# terminator.net
KiCad netlist of a schematic drawn in EAGLE
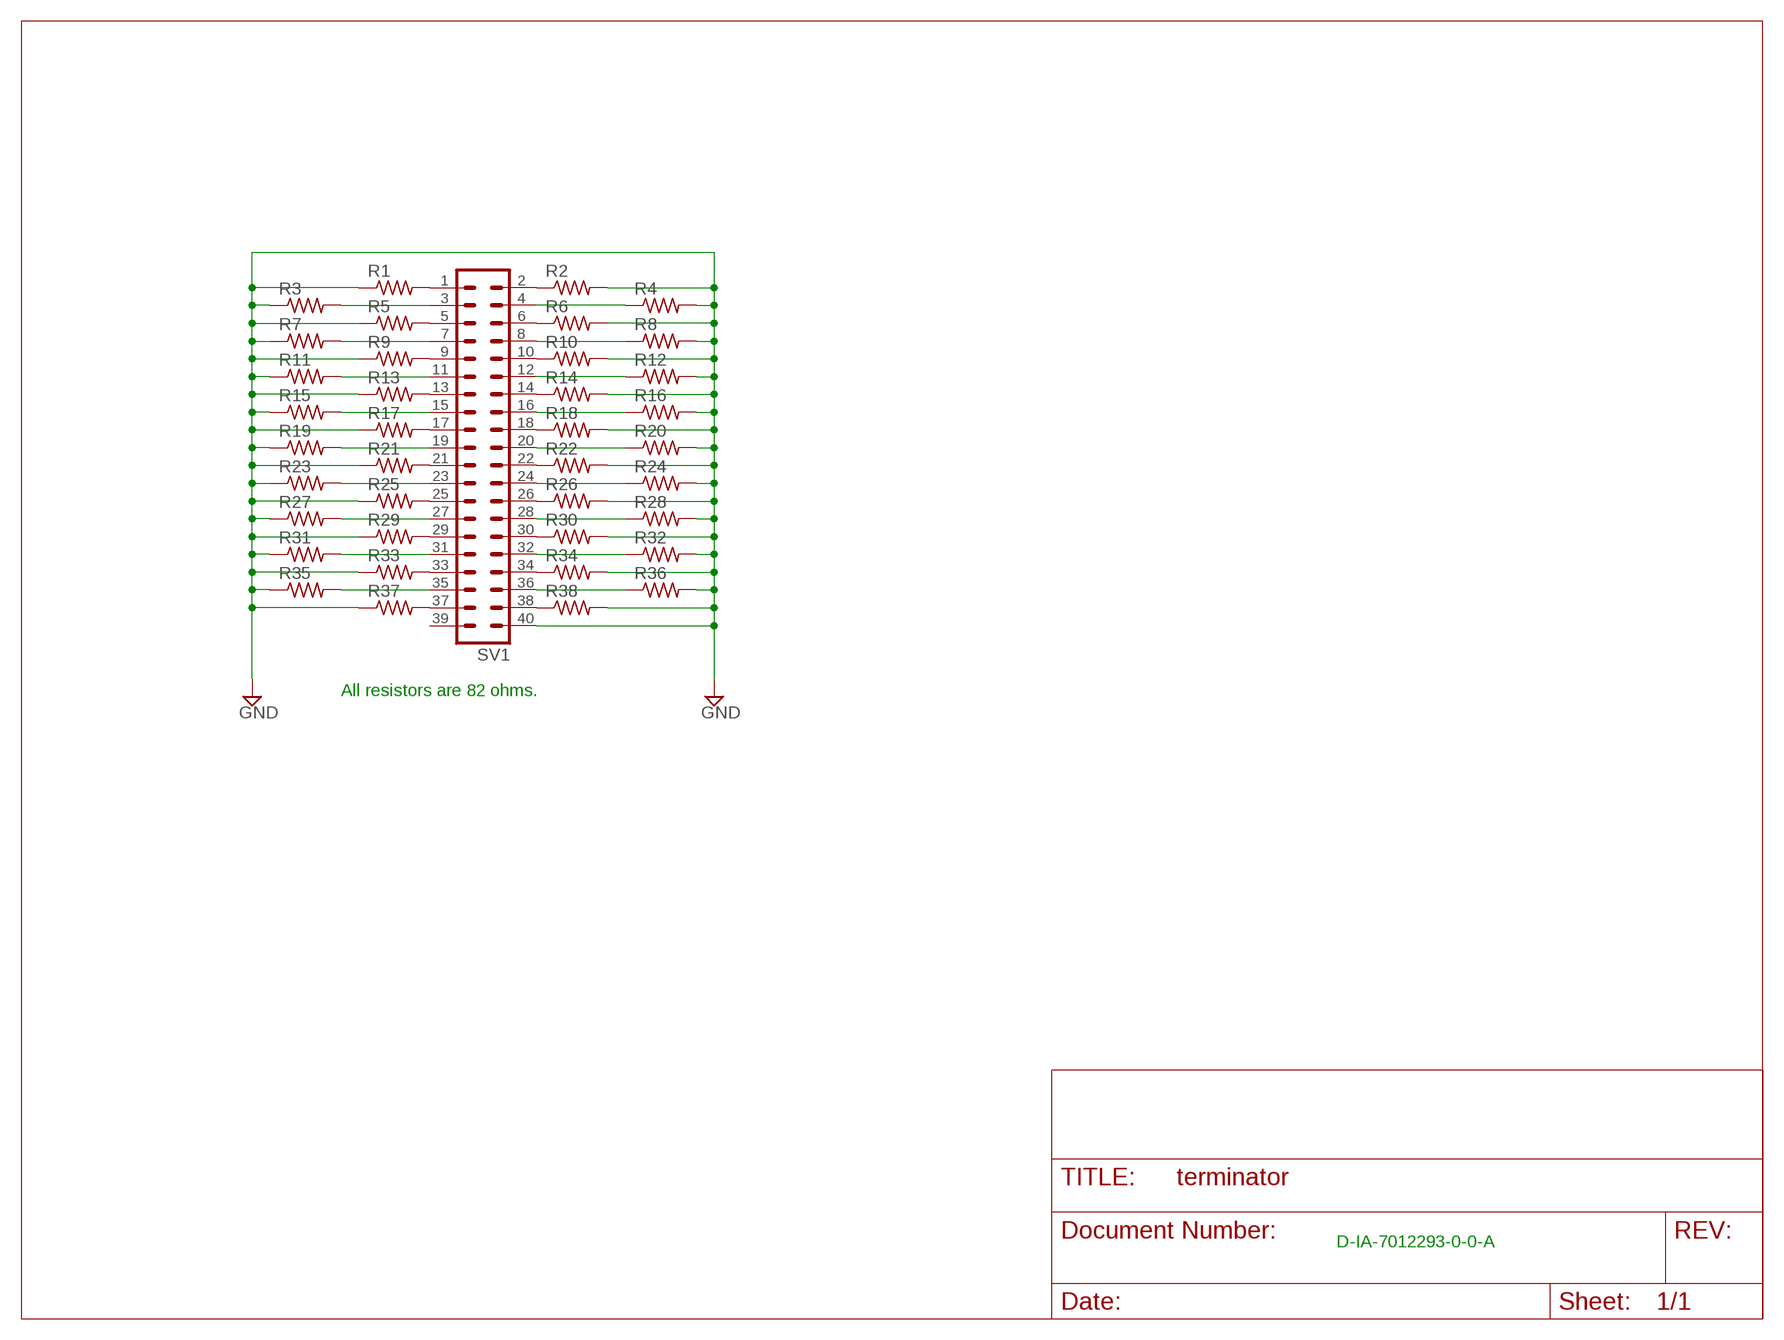
[diagram p0: schematic, sheet 1]

(export (version "E")
  (design (tool "Eeschema 10.0.6"))
  (components
    (comp (ref "R1")
      (value "R-US_M0805")
      (footprint "eagle-import:M0805")
      (libsource (lib "eagle-import") (part "R-US_M0805"))
    )
    (comp (ref "R2")
      (value "R-US_M0805")
      (footprint "eagle-import:M0805")
      (libsource (lib "eagle-import") (part "R-US_M0805"))
    )
    (comp (ref "R3")
      (value "R-US_M0805")
      (footprint "eagle-import:M0805")
      (libsource (lib "eagle-import") (part "R-US_M0805"))
    )
    (comp (ref "R4")
      (value "R-US_M0805")
      (footprint "eagle-import:M0805")
      (libsource (lib "eagle-import") (part "R-US_M0805"))
    )
    (comp (ref "R5")
      (value "R-US_M0805")
      (footprint "eagle-import:M0805")
      (libsource (lib "eagle-import") (part "R-US_M0805"))
    )
    (comp (ref "R6")
      (value "R-US_M0805")
      (footprint "eagle-import:M0805")
      (libsource (lib "eagle-import") (part "R-US_M0805"))
    )
    (comp (ref "R7")
      (value "R-US_M0805")
      (footprint "eagle-import:M0805")
      (libsource (lib "eagle-import") (part "R-US_M0805"))
    )
    (comp (ref "R8")
      (value "R-US_M0805")
      (footprint "eagle-import:M0805")
      (libsource (lib "eagle-import") (part "R-US_M0805"))
    )
    (comp (ref "R9")
      (value "R-US_M0805")
      (footprint "eagle-import:M0805")
      (libsource (lib "eagle-import") (part "R-US_M0805"))
    )
    (comp (ref "R10")
      (value "R-US_M0805")
      (footprint "eagle-import:M0805")
      (libsource (lib "eagle-import") (part "R-US_M0805"))
    )
    (comp (ref "R11")
      (value "R-US_M0805")
      (footprint "eagle-import:M0805")
      (libsource (lib "eagle-import") (part "R-US_M0805"))
    )
    (comp (ref "R12")
      (value "R-US_M0805")
      (footprint "eagle-import:M0805")
      (libsource (lib "eagle-import") (part "R-US_M0805"))
    )
    (comp (ref "R13")
      (value "R-US_M0805")
      (footprint "eagle-import:M0805")
      (libsource (lib "eagle-import") (part "R-US_M0805"))
    )
    (comp (ref "R14")
      (value "R-US_M0805")
      (footprint "eagle-import:M0805")
      (libsource (lib "eagle-import") (part "R-US_M0805"))
    )
    (comp (ref "R15")
      (value "R-US_M0805")
      (footprint "eagle-import:M0805")
      (libsource (lib "eagle-import") (part "R-US_M0805"))
    )
    (comp (ref "R16")
      (value "R-US_M0805")
      (footprint "eagle-import:M0805")
      (libsource (lib "eagle-import") (part "R-US_M0805"))
    )
    (comp (ref "R17")
      (value "R-US_M0805")
      (footprint "eagle-import:M0805")
      (libsource (lib "eagle-import") (part "R-US_M0805"))
    )
    (comp (ref "R18")
      (value "R-US_M0805")
      (footprint "eagle-import:M0805")
      (libsource (lib "eagle-import") (part "R-US_M0805"))
    )
    (comp (ref "R19")
      (value "R-US_M0805")
      (footprint "eagle-import:M0805")
      (libsource (lib "eagle-import") (part "R-US_M0805"))
    )
    (comp (ref "R20")
      (value "R-US_M0805")
      (footprint "eagle-import:M0805")
      (libsource (lib "eagle-import") (part "R-US_M0805"))
    )
    (comp (ref "R21")
      (value "R-US_M0805")
      (footprint "eagle-import:M0805")
      (libsource (lib "eagle-import") (part "R-US_M0805"))
    )
    (comp (ref "R22")
      (value "R-US_M0805")
      (footprint "eagle-import:M0805")
      (libsource (lib "eagle-import") (part "R-US_M0805"))
    )
    (comp (ref "R23")
      (value "R-US_M0805")
      (footprint "eagle-import:M0805")
      (libsource (lib "eagle-import") (part "R-US_M0805"))
    )
    (comp (ref "R24")
      (value "R-US_M0805")
      (footprint "eagle-import:M0805")
      (libsource (lib "eagle-import") (part "R-US_M0805"))
    )
    (comp (ref "R25")
      (value "R-US_M0805")
      (footprint "eagle-import:M0805")
      (libsource (lib "eagle-import") (part "R-US_M0805"))
    )
    (comp (ref "R26")
      (value "R-US_M0805")
      (footprint "eagle-import:M0805")
      (libsource (lib "eagle-import") (part "R-US_M0805"))
    )
    (comp (ref "R27")
      (value "R-US_M0805")
      (footprint "eagle-import:M0805")
      (libsource (lib "eagle-import") (part "R-US_M0805"))
    )
    (comp (ref "R28")
      (value "R-US_M0805")
      (footprint "eagle-import:M0805")
      (libsource (lib "eagle-import") (part "R-US_M0805"))
    )
    (comp (ref "R29")
      (value "R-US_M0805")
      (footprint "eagle-import:M0805")
      (libsource (lib "eagle-import") (part "R-US_M0805"))
    )
    (comp (ref "R30")
      (value "R-US_M0805")
      (footprint "eagle-import:M0805")
      (libsource (lib "eagle-import") (part "R-US_M0805"))
    )
    (comp (ref "R31")
      (value "R-US_M0805")
      (footprint "eagle-import:M0805")
      (libsource (lib "eagle-import") (part "R-US_M0805"))
    )
    (comp (ref "R32")
      (value "R-US_M0805")
      (footprint "eagle-import:M0805")
      (libsource (lib "eagle-import") (part "R-US_M0805"))
    )
    (comp (ref "R33")
      (value "R-US_M0805")
      (footprint "eagle-import:M0805")
      (libsource (lib "eagle-import") (part "R-US_M0805"))
    )
    (comp (ref "R34")
      (value "R-US_M0805")
      (footprint "eagle-import:M0805")
      (libsource (lib "eagle-import") (part "R-US_M0805"))
    )
    (comp (ref "R35")
      (value "R-US_M0805")
      (footprint "eagle-import:M0805")
      (libsource (lib "eagle-import") (part "R-US_M0805"))
    )
    (comp (ref "R36")
      (value "R-US_M0805")
      (footprint "eagle-import:M0805")
      (libsource (lib "eagle-import") (part "R-US_M0805"))
    )
    (comp (ref "R37")
      (value "R-US_M0805")
      (footprint "eagle-import:M0805")
      (libsource (lib "eagle-import") (part "R-US_M0805"))
    )
    (comp (ref "R38")
      (value "R-US_M0805")
      (footprint "eagle-import:M0805")
      (libsource (lib "eagle-import") (part "R-US_M0805"))
    )
    (comp (ref "SV1")
      (value "MA20-2")
      (footprint "eagle-import:MA20-2")
      (libsource (lib "eagle-import") (part "MA20-2"))
    )
  )
  (nets
    (net (code "1") (name "GND") (class "Default")
      (node (ref "R1") (pin "1") (pinfunction "1_1") (pintype "passive"))
      (node (ref "R10") (pin "2") (pinfunction "2_2") (pintype "passive"))
      (node (ref "R11") (pin "1") (pinfunction "1_1") (pintype "passive"))
      (node (ref "R12") (pin "2") (pinfunction "2_2") (pintype "passive"))
      (node (ref "R13") (pin "1") (pinfunction "1_1") (pintype "passive"))
      (node (ref "R14") (pin "2") (pinfunction "2_2") (pintype "passive"))
      (node (ref "R15") (pin "1") (pinfunction "1_1") (pintype "passive"))
      (node (ref "R16") (pin "2") (pinfunction "2_2") (pintype "passive"))
      (node (ref "R17") (pin "1") (pinfunction "1_1") (pintype "passive"))
      (node (ref "R18") (pin "2") (pinfunction "2_2") (pintype "passive"))
      (node (ref "R19") (pin "1") (pinfunction "1_1") (pintype "passive"))
      (node (ref "R2") (pin "2") (pinfunction "2_2") (pintype "passive"))
      (node (ref "R20") (pin "2") (pinfunction "2_2") (pintype "passive"))
      (node (ref "R21") (pin "1") (pinfunction "1_1") (pintype "passive"))
      (node (ref "R22") (pin "2") (pinfunction "2_2") (pintype "passive"))
      (node (ref "R23") (pin "1") (pinfunction "1_1") (pintype "passive"))
      (node (ref "R24") (pin "2") (pinfunction "2_2") (pintype "passive"))
      (node (ref "R25") (pin "1") (pinfunction "1_1") (pintype "passive"))
      (node (ref "R26") (pin "2") (pinfunction "2_2") (pintype "passive"))
      (node (ref "R27") (pin "1") (pinfunction "1_1") (pintype "passive"))
      (node (ref "R28") (pin "2") (pinfunction "2_2") (pintype "passive"))
      (node (ref "R29") (pin "1") (pinfunction "1_1") (pintype "passive"))
      (node (ref "R3") (pin "1") (pinfunction "1_1") (pintype "passive"))
      (node (ref "R30") (pin "2") (pinfunction "2_2") (pintype "passive"))
      (node (ref "R31") (pin "1") (pinfunction "1_1") (pintype "passive"))
      (node (ref "R32") (pin "2") (pinfunction "2_2") (pintype "passive"))
      (node (ref "R33") (pin "1") (pinfunction "1_1") (pintype "passive"))
      (node (ref "R34") (pin "2") (pinfunction "2_2") (pintype "passive"))
      (node (ref "R35") (pin "1") (pinfunction "1_1") (pintype "passive"))
      (node (ref "R36") (pin "2") (pinfunction "2_2") (pintype "passive"))
      (node (ref "R37") (pin "1") (pinfunction "1_1") (pintype "passive"))
      (node (ref "R38") (pin "2") (pinfunction "2_2") (pintype "passive"))
      (node (ref "R4") (pin "2") (pinfunction "2_2") (pintype "passive"))
      (node (ref "R5") (pin "1") (pinfunction "1_1") (pintype "passive"))
      (node (ref "R6") (pin "2") (pinfunction "2_2") (pintype "passive"))
      (node (ref "R7") (pin "1") (pinfunction "1_1") (pintype "passive"))
      (node (ref "R8") (pin "2") (pinfunction "2_2") (pintype "passive"))
      (node (ref "R9") (pin "1") (pinfunction "1_1") (pintype "passive"))
      (node (ref "SV1") (pin "40") (pinfunction "40_40") (pintype "passive"))
    )
    (net (code "2") (name "Net-(R1-Pad2)") (class "Default")
      (node (ref "R1") (pin "2") (pinfunction "2_2") (pintype "passive"))
      (node (ref "SV1") (pin "1") (pinfunction "1_1") (pintype "passive"))
    )
    (net (code "3") (name "Net-(R2-Pad1)") (class "Default")
      (node (ref "R2") (pin "1") (pinfunction "1_1") (pintype "passive"))
      (node (ref "SV1") (pin "2") (pinfunction "2_2") (pintype "passive"))
    )
    (net (code "4") (name "Net-(R3-Pad2)") (class "Default")
      (node (ref "R3") (pin "2") (pinfunction "2_2") (pintype "passive"))
      (node (ref "SV1") (pin "3") (pinfunction "3_3") (pintype "passive"))
    )
    (net (code "5") (name "Net-(R4-Pad1)") (class "Default")
      (node (ref "R4") (pin "1") (pinfunction "1_1") (pintype "passive"))
      (node (ref "SV1") (pin "4") (pinfunction "4_4") (pintype "passive"))
    )
    (net (code "6") (name "Net-(R5-Pad2)") (class "Default")
      (node (ref "R5") (pin "2") (pinfunction "2_2") (pintype "passive"))
      (node (ref "SV1") (pin "5") (pinfunction "5_5") (pintype "passive"))
    )
    (net (code "7") (name "Net-(R6-Pad1)") (class "Default")
      (node (ref "R6") (pin "1") (pinfunction "1_1") (pintype "passive"))
      (node (ref "SV1") (pin "6") (pinfunction "6_6") (pintype "passive"))
    )
    (net (code "8") (name "Net-(R7-Pad2)") (class "Default")
      (node (ref "R7") (pin "2") (pinfunction "2_2") (pintype "passive"))
      (node (ref "SV1") (pin "7") (pinfunction "7_7") (pintype "passive"))
    )
    (net (code "9") (name "Net-(R8-Pad1)") (class "Default")
      (node (ref "R8") (pin "1") (pinfunction "1_1") (pintype "passive"))
      (node (ref "SV1") (pin "8") (pinfunction "8_8") (pintype "passive"))
    )
    (net (code "10") (name "Net-(R9-Pad2)") (class "Default")
      (node (ref "R9") (pin "2") (pinfunction "2_2") (pintype "passive"))
      (node (ref "SV1") (pin "9") (pinfunction "9_9") (pintype "passive"))
    )
    (net (code "11") (name "Net-(R10-Pad1)") (class "Default")
      (node (ref "R10") (pin "1") (pinfunction "1_1") (pintype "passive"))
      (node (ref "SV1") (pin "10") (pinfunction "10_10") (pintype "passive"))
    )
    (net (code "12") (name "Net-(R11-Pad2)") (class "Default")
      (node (ref "R11") (pin "2") (pinfunction "2_2") (pintype "passive"))
      (node (ref "SV1") (pin "11") (pinfunction "11_11") (pintype "passive"))
    )
    (net (code "13") (name "Net-(R12-Pad1)") (class "Default")
      (node (ref "R12") (pin "1") (pinfunction "1_1") (pintype "passive"))
      (node (ref "SV1") (pin "12") (pinfunction "12_12") (pintype "passive"))
    )
    (net (code "14") (name "Net-(R13-Pad2)") (class "Default")
      (node (ref "R13") (pin "2") (pinfunction "2_2") (pintype "passive"))
      (node (ref "SV1") (pin "13") (pinfunction "13_13") (pintype "passive"))
    )
    (net (code "15") (name "Net-(R14-Pad1)") (class "Default")
      (node (ref "R14") (pin "1") (pinfunction "1_1") (pintype "passive"))
      (node (ref "SV1") (pin "14") (pinfunction "14_14") (pintype "passive"))
    )
    (net (code "16") (name "Net-(R15-Pad2)") (class "Default")
      (node (ref "R15") (pin "2") (pinfunction "2_2") (pintype "passive"))
      (node (ref "SV1") (pin "15") (pinfunction "15_15") (pintype "passive"))
    )
    (net (code "17") (name "Net-(R16-Pad1)") (class "Default")
      (node (ref "R16") (pin "1") (pinfunction "1_1") (pintype "passive"))
      (node (ref "SV1") (pin "16") (pinfunction "16_16") (pintype "passive"))
    )
    (net (code "18") (name "Net-(R17-Pad2)") (class "Default")
      (node (ref "R17") (pin "2") (pinfunction "2_2") (pintype "passive"))
      (node (ref "SV1") (pin "17") (pinfunction "17_17") (pintype "passive"))
    )
    (net (code "19") (name "Net-(R18-Pad1)") (class "Default")
      (node (ref "R18") (pin "1") (pinfunction "1_1") (pintype "passive"))
      (node (ref "SV1") (pin "18") (pinfunction "18_18") (pintype "passive"))
    )
    (net (code "20") (name "Net-(R19-Pad2)") (class "Default")
      (node (ref "R19") (pin "2") (pinfunction "2_2") (pintype "passive"))
      (node (ref "SV1") (pin "19") (pinfunction "19_19") (pintype "passive"))
    )
    (net (code "21") (name "Net-(R20-Pad1)") (class "Default")
      (node (ref "R20") (pin "1") (pinfunction "1_1") (pintype "passive"))
      (node (ref "SV1") (pin "20") (pinfunction "20_20") (pintype "passive"))
    )
    (net (code "22") (name "Net-(R21-Pad2)") (class "Default")
      (node (ref "R21") (pin "2") (pinfunction "2_2") (pintype "passive"))
      (node (ref "SV1") (pin "21") (pinfunction "21_21") (pintype "passive"))
    )
    (net (code "23") (name "Net-(R22-Pad1)") (class "Default")
      (node (ref "R22") (pin "1") (pinfunction "1_1") (pintype "passive"))
      (node (ref "SV1") (pin "22") (pinfunction "22_22") (pintype "passive"))
    )
    (net (code "24") (name "Net-(R23-Pad2)") (class "Default")
      (node (ref "R23") (pin "2") (pinfunction "2_2") (pintype "passive"))
      (node (ref "SV1") (pin "23") (pinfunction "23_23") (pintype "passive"))
    )
    (net (code "25") (name "Net-(R24-Pad1)") (class "Default")
      (node (ref "R24") (pin "1") (pinfunction "1_1") (pintype "passive"))
      (node (ref "SV1") (pin "24") (pinfunction "24_24") (pintype "passive"))
    )
    (net (code "26") (name "Net-(R25-Pad2)") (class "Default")
      (node (ref "R25") (pin "2") (pinfunction "2_2") (pintype "passive"))
      (node (ref "SV1") (pin "25") (pinfunction "25_25") (pintype "passive"))
    )
    (net (code "27") (name "Net-(R26-Pad1)") (class "Default")
      (node (ref "R26") (pin "1") (pinfunction "1_1") (pintype "passive"))
      (node (ref "SV1") (pin "26") (pinfunction "26_26") (pintype "passive"))
    )
    (net (code "28") (name "Net-(R27-Pad2)") (class "Default")
      (node (ref "R27") (pin "2") (pinfunction "2_2") (pintype "passive"))
      (node (ref "SV1") (pin "27") (pinfunction "27_27") (pintype "passive"))
    )
    (net (code "29") (name "Net-(R28-Pad1)") (class "Default")
      (node (ref "R28") (pin "1") (pinfunction "1_1") (pintype "passive"))
      (node (ref "SV1") (pin "28") (pinfunction "28_28") (pintype "passive"))
    )
    (net (code "30") (name "Net-(R29-Pad2)") (class "Default")
      (node (ref "R29") (pin "2") (pinfunction "2_2") (pintype "passive"))
      (node (ref "SV1") (pin "29") (pinfunction "29_29") (pintype "passive"))
    )
    (net (code "31") (name "Net-(R30-Pad1)") (class "Default")
      (node (ref "R30") (pin "1") (pinfunction "1_1") (pintype "passive"))
      (node (ref "SV1") (pin "30") (pinfunction "30_30") (pintype "passive"))
    )
    (net (code "32") (name "Net-(R31-Pad2)") (class "Default")
      (node (ref "R31") (pin "2") (pinfunction "2_2") (pintype "passive"))
      (node (ref "SV1") (pin "31") (pinfunction "31_31") (pintype "passive"))
    )
    (net (code "33") (name "Net-(R32-Pad1)") (class "Default")
      (node (ref "R32") (pin "1") (pinfunction "1_1") (pintype "passive"))
      (node (ref "SV1") (pin "32") (pinfunction "32_32") (pintype "passive"))
    )
    (net (code "34") (name "Net-(R33-Pad2)") (class "Default")
      (node (ref "R33") (pin "2") (pinfunction "2_2") (pintype "passive"))
      (node (ref "SV1") (pin "33") (pinfunction "33_33") (pintype "passive"))
    )
    (net (code "35") (name "Net-(R34-Pad1)") (class "Default")
      (node (ref "R34") (pin "1") (pinfunction "1_1") (pintype "passive"))
      (node (ref "SV1") (pin "34") (pinfunction "34_34") (pintype "passive"))
    )
    (net (code "36") (name "Net-(R35-Pad2)") (class "Default")
      (node (ref "R35") (pin "2") (pinfunction "2_2") (pintype "passive"))
      (node (ref "SV1") (pin "35") (pinfunction "35_35") (pintype "passive"))
    )
    (net (code "37") (name "Net-(R36-Pad1)") (class "Default")
      (node (ref "R36") (pin "1") (pinfunction "1_1") (pintype "passive"))
      (node (ref "SV1") (pin "36") (pinfunction "36_36") (pintype "passive"))
    )
    (net (code "38") (name "Net-(R37-Pad2)") (class "Default")
      (node (ref "R37") (pin "2") (pinfunction "2_2") (pintype "passive"))
      (node (ref "SV1") (pin "37") (pinfunction "37_37") (pintype "passive"))
    )
    (net (code "39") (name "Net-(R38-Pad1)") (class "Default")
      (node (ref "R38") (pin "1") (pinfunction "1_1") (pintype "passive"))
      (node (ref "SV1") (pin "38") (pinfunction "38_38") (pintype "passive"))
    )
    (net (code "40") (name "unconnected-(SV1-Pad39)") (class "Default")
      (node (ref "SV1") (pin "39") (pinfunction "39_39") (pintype "passive"))
    )
  )
)
